# detector_ne602.net
KiCad netlist of a schematic drawn in EAGLE
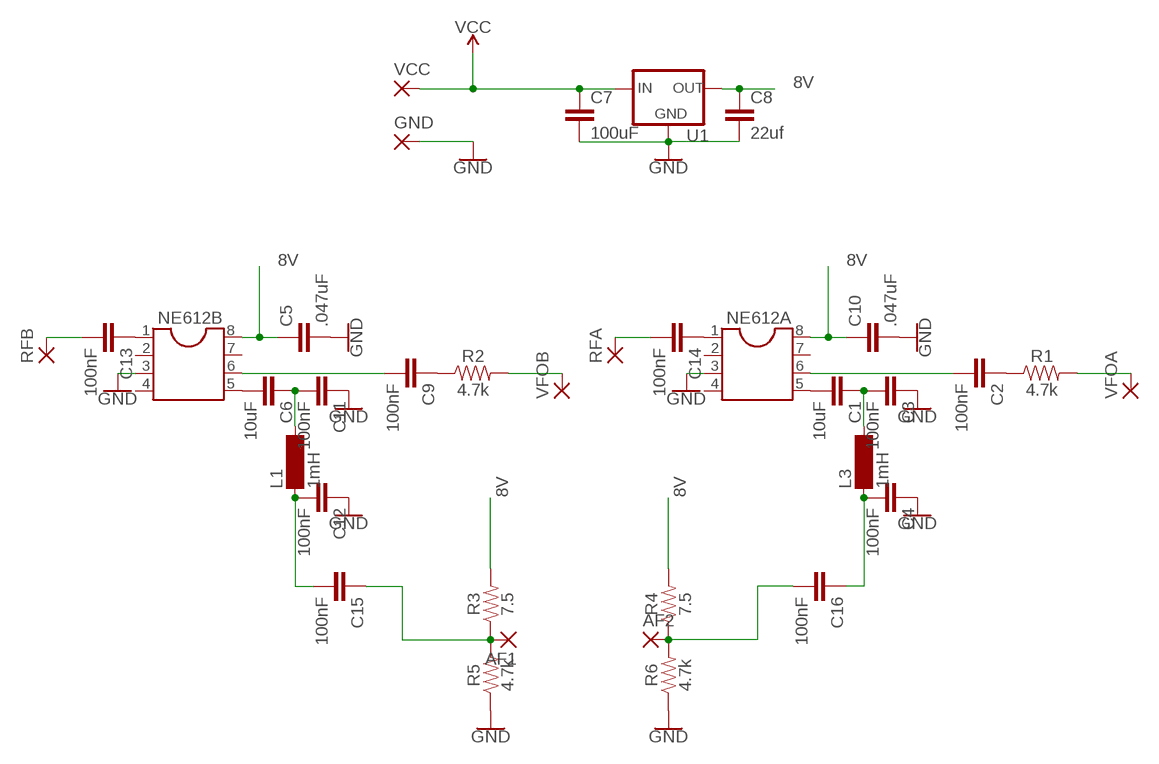
[diagram p0: schematic, sheet 1]

(export (version "E")
  (design (tool "Eeschema 10.0.6"))
  (components
    (comp (ref "AF1")
      (value "3,17/1,1")
      (footprint "eagle-import:3,17_1,1")
      (libsource (lib "eagle-import") (part "3,17/1,1"))
    )
    (comp (ref "AF2")
      (value "3,17/1,1")
      (footprint "eagle-import:3,17_1,1")
      (libsource (lib "eagle-import") (part "3,17/1,1"))
    )
    (comp (ref "C1")
      (value "10uF")
      (footprint "eagle-import:C5B3.5")
      (libsource (lib "eagle-import") (part "C5/3.5"))
    )
    (comp (ref "C2")
      (value "100nF")
      (footprint "eagle-import:C5B3.5")
      (libsource (lib "eagle-import") (part "C5/3.5"))
    )
    (comp (ref "C3")
      (value "100nF")
      (footprint "eagle-import:C5B3.5")
      (libsource (lib "eagle-import") (part "C5/3.5"))
    )
    (comp (ref "C4")
      (value "100nF")
      (footprint "eagle-import:C5B3.5")
      (libsource (lib "eagle-import") (part "C5/3.5"))
    )
    (comp (ref "C5")
      (value ".047uF")
      (footprint "eagle-import:C5B3.5")
      (libsource (lib "eagle-import") (part "C5/3.5"))
    )
    (comp (ref "C6")
      (value "10uF")
      (footprint "eagle-import:C5B3.5")
      (libsource (lib "eagle-import") (part "C5/3.5"))
    )
    (comp (ref "C7")
      (value "100uF")
      (footprint "eagle-import:C5B3.5")
      (libsource (lib "eagle-import") (part "C5/3.5"))
    )
    (comp (ref "C8")
      (value "22uf")
      (footprint "eagle-import:C5B3.5")
      (libsource (lib "eagle-import") (part "C5/3.5"))
    )
    (comp (ref "C9")
      (value "100nF")
      (footprint "eagle-import:C5B3.5")
      (libsource (lib "eagle-import") (part "C5/3.5"))
    )
    (comp (ref "C10")
      (value ".047uF")
      (footprint "eagle-import:C5B3.5")
      (libsource (lib "eagle-import") (part "C5/3.5"))
    )
    (comp (ref "C11")
      (value "100nF")
      (footprint "eagle-import:C5B3.5")
      (libsource (lib "eagle-import") (part "C5/3.5"))
    )
    (comp (ref "C12")
      (value "100nF")
      (footprint "eagle-import:C5B3.5")
      (libsource (lib "eagle-import") (part "C5/3.5"))
    )
    (comp (ref "C13")
      (value "100nF")
      (footprint "eagle-import:C5B3.5")
      (libsource (lib "eagle-import") (part "C5/3.5"))
    )
    (comp (ref "C14")
      (value "100nF")
      (footprint "eagle-import:C5B3.5")
      (libsource (lib "eagle-import") (part "C5/3.5"))
    )
    (comp (ref "C15")
      (value "100nF")
      (footprint "eagle-import:C5B3.5")
      (libsource (lib "eagle-import") (part "C5/3.5"))
    )
    (comp (ref "C16")
      (value "100nF")
      (footprint "eagle-import:C5B3.5")
      (libsource (lib "eagle-import") (part "C5/3.5"))
    )
    (comp (ref "GND")
      (value "3,17/1,1")
      (footprint "eagle-import:3,17_1,1")
      (libsource (lib "eagle-import") (part "3,17/1,1"))
    )
    (comp (ref "L1")
      (value "1mH")
      (footprint "eagle-import:BS75")
      (libsource (lib "eagle-import") (part "BS75"))
    )
    (comp (ref "L3")
      (value "1mH")
      (footprint "eagle-import:BS75")
      (libsource (lib "eagle-import") (part "BS75"))
    )
    (comp (ref "NE612A")
      (value "DIL8")
      (footprint "eagle-import:DIL08")
      (libsource (lib "eagle-import") (part "DIL8"))
    )
    (comp (ref "NE612B")
      (value "DIL8")
      (footprint "eagle-import:DIL08")
      (libsource (lib "eagle-import") (part "DIL8"))
    )
    (comp (ref "R1")
      (value "4.7k")
      (footprint "eagle-import:AXIAL-0.3")
      (libsource (lib "eagle-import") (part "1KOHM-HORIZ-1/4W-1%"))
    )
    (comp (ref "R2")
      (value "4.7k")
      (footprint "eagle-import:AXIAL-0.3")
      (libsource (lib "eagle-import") (part "1KOHM-HORIZ-1/4W-1%"))
    )
    (comp (ref "R3")
      (value "7.5")
      (footprint "eagle-import:AXIAL-0.3")
      (libsource (lib "eagle-import") (part "1KOHM-HORIZ-1/4W-1%"))
    )
    (comp (ref "R4")
      (value "7.5")
      (footprint "eagle-import:AXIAL-0.3")
      (libsource (lib "eagle-import") (part "1KOHM-HORIZ-1/4W-1%"))
    )
    (comp (ref "R5")
      (value "4.7k")
      (footprint "eagle-import:AXIAL-0.3")
      (libsource (lib "eagle-import") (part "1KOHM-HORIZ-1/4W-1%"))
    )
    (comp (ref "R6")
      (value "4.7k")
      (footprint "eagle-import:AXIAL-0.3")
      (libsource (lib "eagle-import") (part "1KOHM-HORIZ-1/4W-1%"))
    )
    (comp (ref "RFA")
      (value "3,17/1,1")
      (footprint "eagle-import:3,17_1,1")
      (libsource (lib "eagle-import") (part "3,17/1,1"))
    )
    (comp (ref "RFB")
      (value "3,17/1,1")
      (footprint "eagle-import:3,17_1,1")
      (libsource (lib "eagle-import") (part "3,17/1,1"))
    )
    (comp (ref "U1")
      (value "V_REG_78XXTO-92_UNTESTED")
      (footprint "eagle-import:TO-92")
      (libsource (lib "eagle-import") (part "V_REG_78XXTO-92_UNTESTED"))
    )
    (comp (ref "VCC")
      (value "3,17/1,1")
      (footprint "eagle-import:3,17_1,1")
      (libsource (lib "eagle-import") (part "3,17/1,1"))
    )
    (comp (ref "VFOA")
      (value "3,17/1,1")
      (footprint "eagle-import:3,17_1,1")
      (libsource (lib "eagle-import") (part "3,17/1,1"))
    )
    (comp (ref "VFOB")
      (value "3,17/1,1")
      (footprint "eagle-import:3,17_1,1")
      (libsource (lib "eagle-import") (part "3,17/1,1"))
    )
  )
  (nets
    (net (code "1") (name "/8V") (class "Default")
      (node (ref "C10") (pin "1") (pinfunction "1_1") (pintype "passive"))
      (node (ref "C5") (pin "1") (pinfunction "1_1") (pintype "passive"))
      (node (ref "C8") (pin "1") (pinfunction "1_1") (pintype "passive"))
      (node (ref "NE612A") (pin "8") (pinfunction "8_8") (pintype "passive"))
      (node (ref "NE612B") (pin "8") (pinfunction "8_8") (pintype "passive"))
      (node (ref "R3") (pin "P$2") (pinfunction "2_P$2") (pintype "passive"))
      (node (ref "R4") (pin "P$2") (pinfunction "2_P$2") (pintype "passive"))
      (node (ref "U1") (pin "1") (pinfunction "OUT_1") (pintype "passive"))
    )
    (net (code "2") (name "GND") (class "Default")
      (node (ref "C10") (pin "2") (pinfunction "2_2") (pintype "passive"))
      (node (ref "C11") (pin "1") (pinfunction "1_1") (pintype "passive"))
      (node (ref "C12") (pin "1") (pinfunction "1_1") (pintype "passive"))
      (node (ref "C3") (pin "1") (pinfunction "1_1") (pintype "passive"))
      (node (ref "C4") (pin "1") (pinfunction "1_1") (pintype "passive"))
      (node (ref "C5") (pin "2") (pinfunction "2_2") (pintype "passive"))
      (node (ref "C7") (pin "2") (pinfunction "2_2") (pintype "passive"))
      (node (ref "C8") (pin "2") (pinfunction "2_2") (pintype "passive"))
      (node (ref "GND") (pin "1") (pinfunction "P_1") (pintype "passive"))
      (node (ref "NE612A") (pin "3") (pinfunction "3_3") (pintype "passive"))
      (node (ref "NE612B") (pin "3") (pinfunction "3_3") (pintype "passive"))
      (node (ref "R5") (pin "P$1") (pinfunction "1_P$1") (pintype "passive"))
      (node (ref "R6") (pin "P$1") (pinfunction "1_P$1") (pintype "passive"))
      (node (ref "U1") (pin "2") (pinfunction "GND_2") (pintype "input"))
    )
    (net (code "3") (name "Net-(AF1-P)") (class "Default")
      (node (ref "AF1") (pin "1") (pinfunction "P_1") (pintype "passive"))
      (node (ref "C15") (pin "1") (pinfunction "1_1") (pintype "passive"))
      (node (ref "R3") (pin "P$1") (pinfunction "1_P$1") (pintype "passive"))
      (node (ref "R5") (pin "P$2") (pinfunction "2_P$2") (pintype "passive"))
    )
    (net (code "4") (name "Net-(AF2-P)") (class "Default")
      (node (ref "AF2") (pin "1") (pinfunction "P_1") (pintype "passive"))
      (node (ref "C16") (pin "2") (pinfunction "2_2") (pintype "passive"))
      (node (ref "R4") (pin "P$1") (pinfunction "1_P$1") (pintype "passive"))
      (node (ref "R6") (pin "P$2") (pinfunction "2_P$2") (pintype "passive"))
    )
    (net (code "5") (name "Net-(C1-Pad1)") (class "Default")
      (node (ref "C1") (pin "1") (pinfunction "1_1") (pintype "passive"))
      (node (ref "C3") (pin "2") (pinfunction "2_2") (pintype "passive"))
      (node (ref "L3") (pin "2") (pinfunction "2_2") (pintype "passive"))
    )
    (net (code "6") (name "Net-(C1-Pad2)") (class "Default")
      (node (ref "C1") (pin "2") (pinfunction "2_2") (pintype "passive"))
      (node (ref "NE612A") (pin "5") (pinfunction "5_5") (pintype "passive"))
    )
    (net (code "7") (name "Net-(C2-Pad2)") (class "Default")
      (node (ref "C2") (pin "2") (pinfunction "2_2") (pintype "passive"))
      (node (ref "NE612A") (pin "6") (pinfunction "6_6") (pintype "passive"))
    )
    (net (code "8") (name "Net-(C6-Pad2)") (class "Default")
      (node (ref "C6") (pin "2") (pinfunction "2_2") (pintype "passive"))
      (node (ref "NE612B") (pin "5") (pinfunction "5_5") (pintype "passive"))
    )
    (net (code "9") (name "Net-(C9-Pad2)") (class "Default")
      (node (ref "C9") (pin "2") (pinfunction "2_2") (pintype "passive"))
      (node (ref "NE612B") (pin "6") (pinfunction "6_6") (pintype "passive"))
    )
    (net (code "10") (name "Net-(C11-Pad2)") (class "Default")
      (node (ref "C11") (pin "2") (pinfunction "2_2") (pintype "passive"))
      (node (ref "C6") (pin "1") (pinfunction "1_1") (pintype "passive"))
      (node (ref "L1") (pin "2") (pinfunction "2_2") (pintype "passive"))
    )
    (net (code "11") (name "Net-(C12-Pad2)") (class "Default")
      (node (ref "C12") (pin "2") (pinfunction "2_2") (pintype "passive"))
      (node (ref "C15") (pin "2") (pinfunction "2_2") (pintype "passive"))
      (node (ref "L1") (pin "1") (pinfunction "1_1") (pintype "passive"))
    )
    (net (code "12") (name "Net-(C13-Pad1)") (class "Default")
      (node (ref "C13") (pin "1") (pinfunction "1_1") (pintype "passive"))
      (node (ref "NE612B") (pin "1") (pinfunction "1_1") (pintype "passive"))
    )
    (net (code "13") (name "Net-(C14-Pad1)") (class "Default")
      (node (ref "C14") (pin "1") (pinfunction "1_1") (pintype "passive"))
      (node (ref "NE612A") (pin "1") (pinfunction "1_1") (pintype "passive"))
    )
    (net (code "14") (name "Net-(C16-Pad1)") (class "Default")
      (node (ref "C16") (pin "1") (pinfunction "1_1") (pintype "passive"))
      (node (ref "C4") (pin "2") (pinfunction "2_2") (pintype "passive"))
      (node (ref "L3") (pin "1") (pinfunction "1_1") (pintype "passive"))
    )
    (net (code "15") (name "Net-(R1-1)") (class "Default")
      (node (ref "C2") (pin "1") (pinfunction "1_1") (pintype "passive"))
      (node (ref "R1") (pin "P$1") (pinfunction "1_P$1") (pintype "passive"))
    )
    (net (code "16") (name "Net-(R1-2)") (class "Default")
      (node (ref "R1") (pin "P$2") (pinfunction "2_P$2") (pintype "passive"))
      (node (ref "VFOA") (pin "1") (pinfunction "P_1") (pintype "passive"))
    )
    (net (code "17") (name "Net-(R2-1)") (class "Default")
      (node (ref "C9") (pin "1") (pinfunction "1_1") (pintype "passive"))
      (node (ref "R2") (pin "P$1") (pinfunction "1_P$1") (pintype "passive"))
    )
    (net (code "18") (name "Net-(R2-2)") (class "Default")
      (node (ref "R2") (pin "P$2") (pinfunction "2_P$2") (pintype "passive"))
      (node (ref "VFOB") (pin "1") (pinfunction "P_1") (pintype "passive"))
    )
    (net (code "19") (name "Net-(RFA-P)") (class "Default")
      (node (ref "C14") (pin "2") (pinfunction "2_2") (pintype "passive"))
      (node (ref "RFA") (pin "1") (pinfunction "P_1") (pintype "passive"))
    )
    (net (code "20") (name "Net-(RFB-P)") (class "Default")
      (node (ref "C13") (pin "2") (pinfunction "2_2") (pintype "passive"))
      (node (ref "RFB") (pin "1") (pinfunction "P_1") (pintype "passive"))
    )
    (net (code "21") (name "VCC") (class "Default")
      (node (ref "C7") (pin "1") (pinfunction "1_1") (pintype "passive"))
      (node (ref "U1") (pin "3") (pinfunction "IN_3") (pintype "input"))
      (node (ref "VCC") (pin "1") (pinfunction "P_1") (pintype "passive"))
    )
    (net (code "22") (name "unconnected-(NE612A-Pad2)") (class "Default")
      (node (ref "NE612A") (pin "2") (pinfunction "2_2") (pintype "passive"))
    )
    (net (code "23") (name "unconnected-(NE612A-Pad4)") (class "Default")
      (node (ref "NE612A") (pin "4") (pinfunction "4_4") (pintype "passive"))
    )
    (net (code "24") (name "unconnected-(NE612A-Pad7)") (class "Default")
      (node (ref "NE612A") (pin "7") (pinfunction "7_7") (pintype "passive"))
    )
    (net (code "25") (name "unconnected-(NE612B-Pad2)") (class "Default")
      (node (ref "NE612B") (pin "2") (pinfunction "2_2") (pintype "passive"))
    )
    (net (code "26") (name "unconnected-(NE612B-Pad4)") (class "Default")
      (node (ref "NE612B") (pin "4") (pinfunction "4_4") (pintype "passive"))
    )
    (net (code "27") (name "unconnected-(NE612B-Pad7)") (class "Default")
      (node (ref "NE612B") (pin "7") (pinfunction "7_7") (pintype "passive"))
    )
  )
)
